# AS226279_ECE319K_Baseline_Schematic.net
KiCad netlist of a schematic drawn in EAGLE
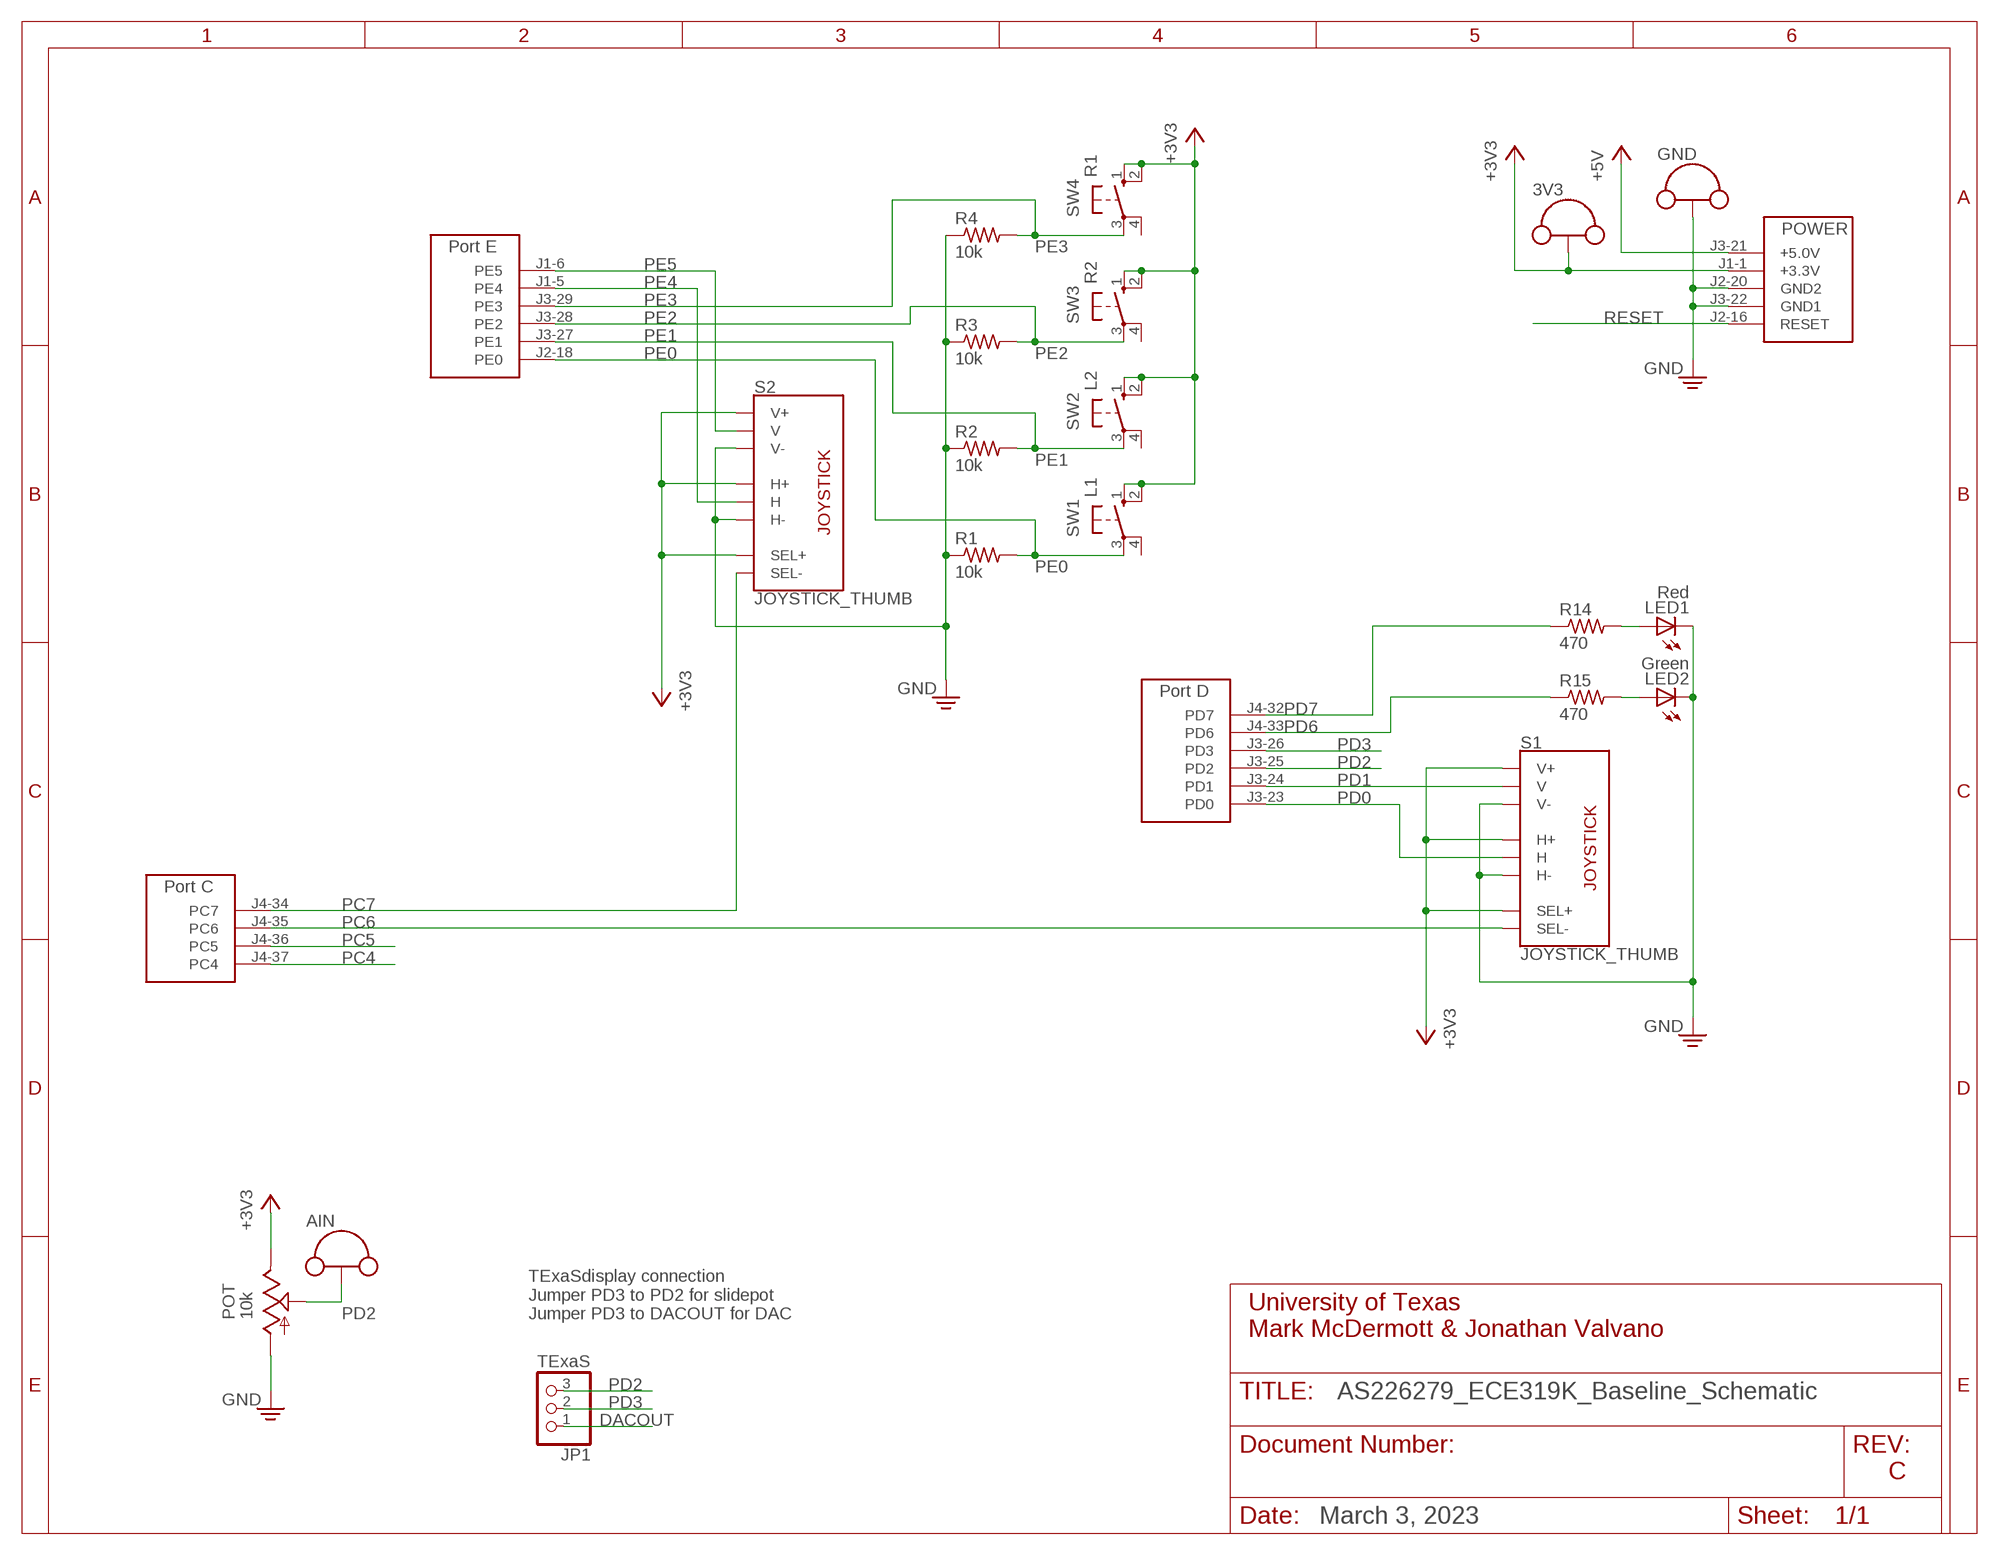
[diagram p0: schematic, sheet 1, part 1 of 2]
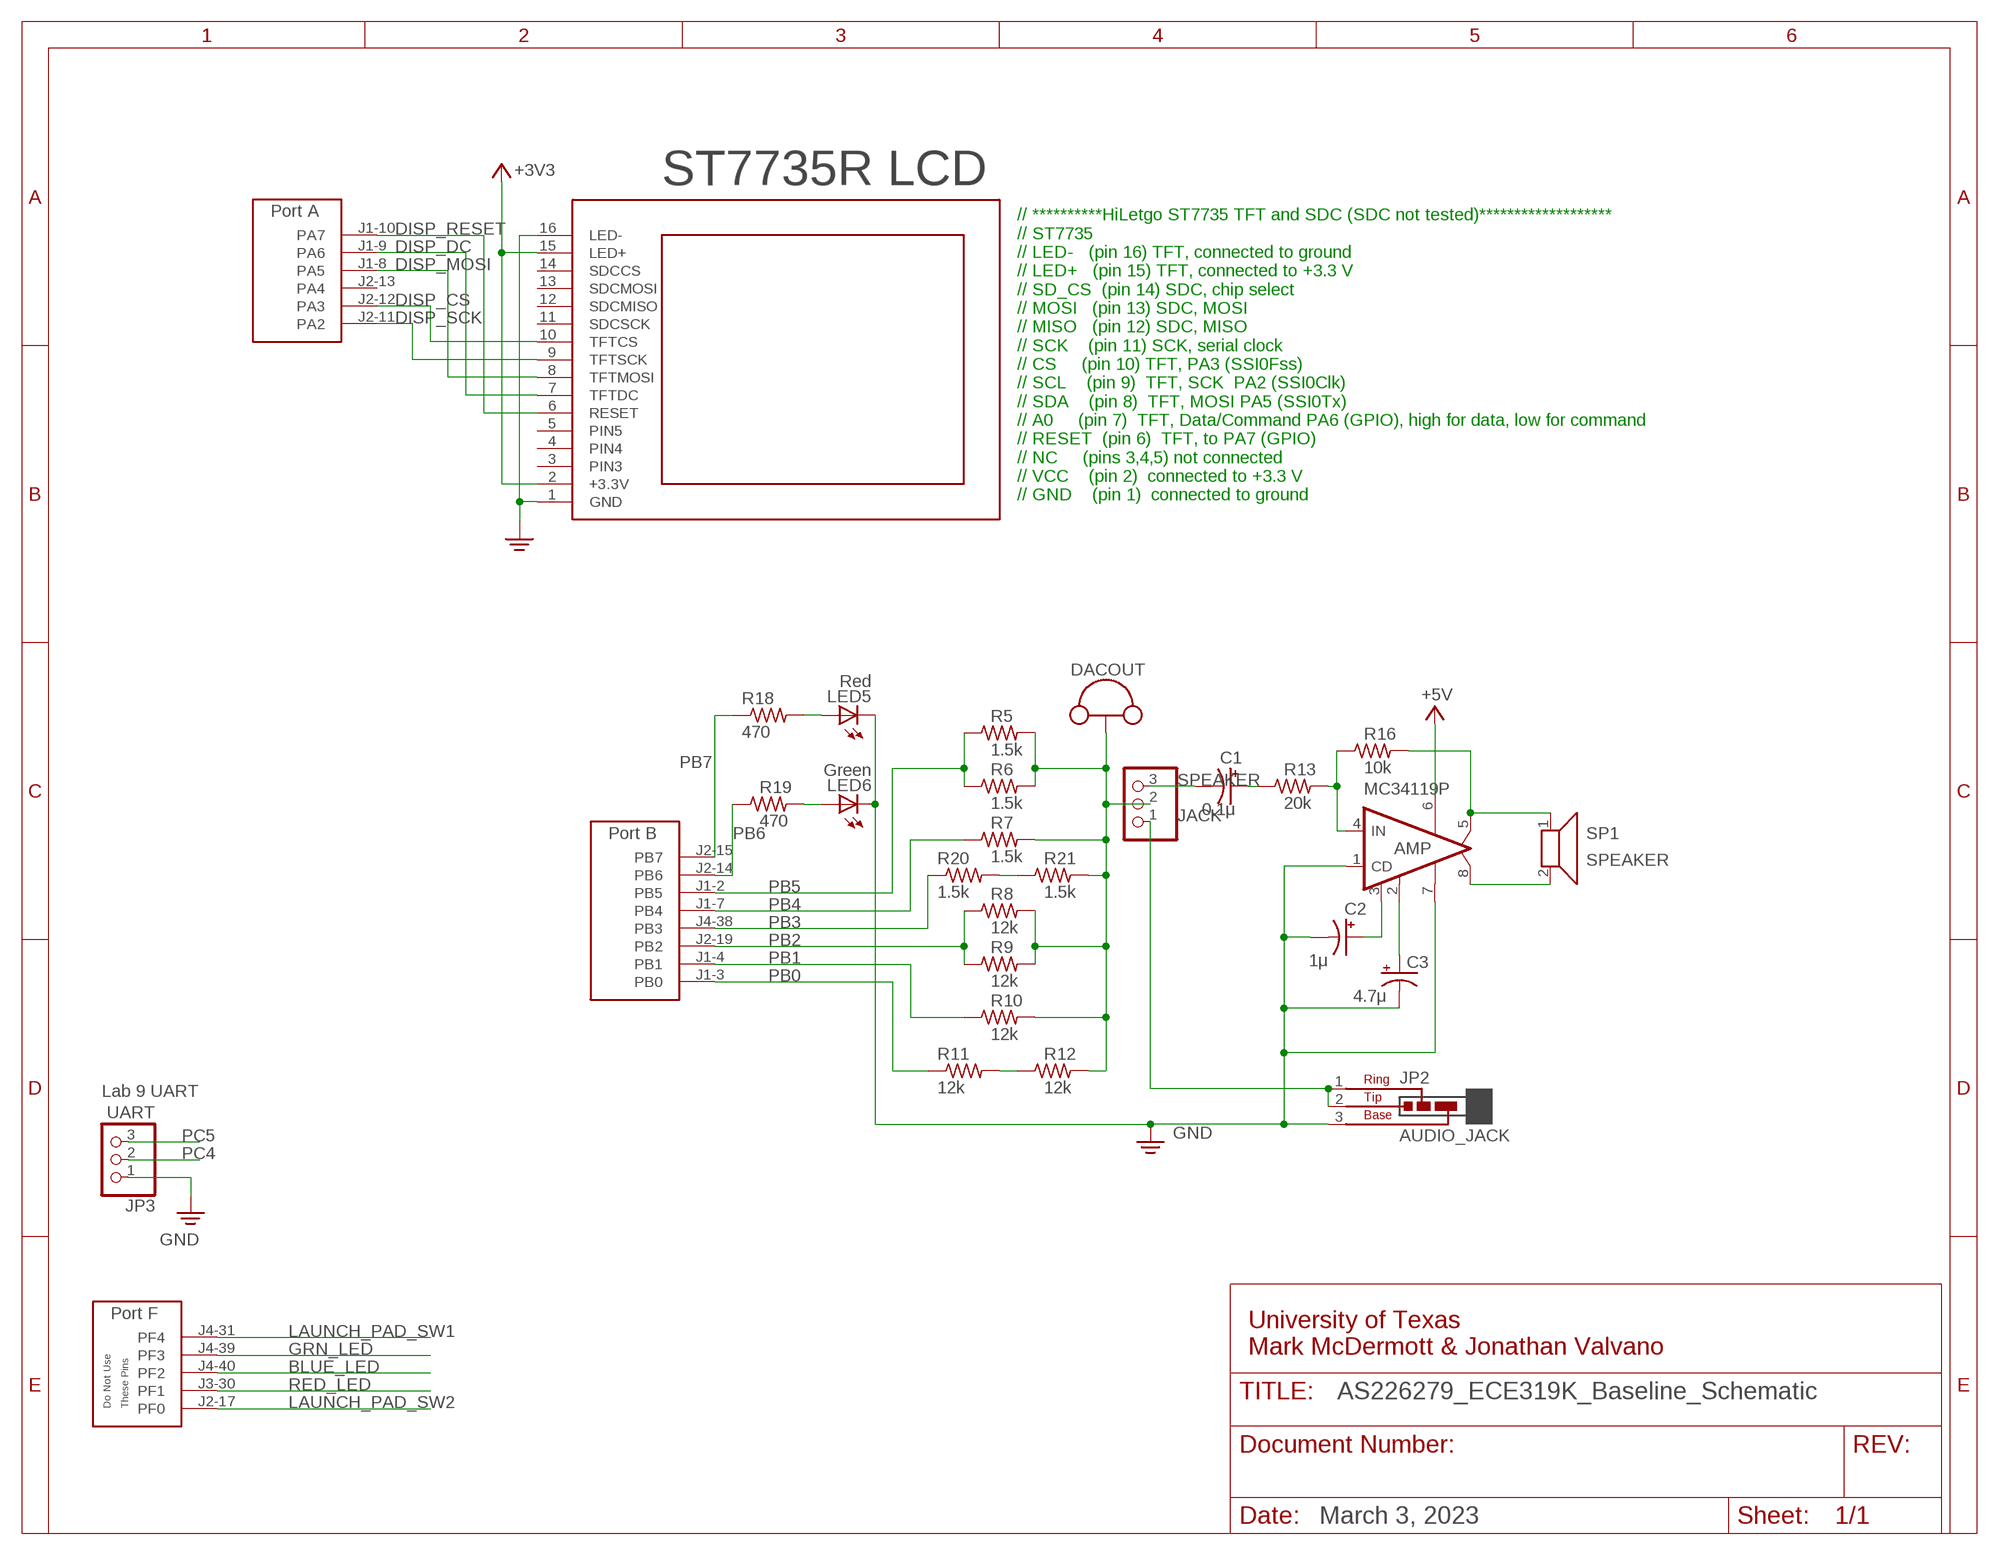
[diagram p1: schematic, sheet 1, part 2 of 2]

(export (version "E")
  (design (tool "Eeschema 10.0.6"))
  (components
    (comp (ref "3V3")
      (value "TP_LOOP")
      (footprint "eagle-import:TP_LOOP")
      (libsource (lib "eagle-import") (part "TP_LOOP"))
    )
    (comp (ref "AIN")
      (value "TP_LOOP")
      (footprint "eagle-import:TP_LOOP")
      (libsource (lib "eagle-import") (part "TP_LOOP"))
    )
    (comp (ref "AMP")
      (value "MC34119P")
      (footprint "eagle-import:DIL08")
      (libsource (lib "eagle-import") (part "MC34119P"))
    )
    (comp (ref "C1")
      (value "0.1μ")
      (footprint "eagle-import:CAP200MILPOLARIZED")
      (libsource (lib "eagle-import") (part "CAPACITOR_POLARIZEDE5-6"))
    )
    (comp (ref "C2")
      (value "1μ")
      (footprint "eagle-import:CAP200MILPOLARIZED")
      (libsource (lib "eagle-import") (part "CAPACITOR_POLARIZEDE5-6"))
    )
    (comp (ref "C3")
      (value "4.7μ")
      (footprint "eagle-import:CAP200MILPOLARIZED")
      (libsource (lib "eagle-import") (part "CAPACITOR_POLARIZEDE5-6"))
    )
    (comp (ref "DACOUT")
      (value "TP_LOOP")
      (footprint "eagle-import:TP_LOOP")
      (libsource (lib "eagle-import") (part "TP_LOOP"))
    )
    (comp (ref "DACOUT_HEADER")
      (value "TExaS")
      (footprint "eagle-import:1X03")
      (libsource (lib "eagle-import") (part "PINHD-1X3"))
    )
    (comp (ref "GND")
      (value "TP_LOOP")
      (footprint "eagle-import:TP_LOOP")
      (libsource (lib "eagle-import") (part "TP_LOOP"))
    )
    (comp (ref "JP1")
      (value "TExaS")
      (footprint "eagle-import:1X03")
      (libsource (lib "eagle-import") (part "PINHD-1X3"))
    )
    (comp (ref "JP2")
      (value "AUDIO_JACK")
      (footprint "eagle-import:JACK")
      (libsource (lib "eagle-import") (part "AUDIO_JACK"))
    )
    (comp (ref "JP3")
      (value "UART")
      (footprint "eagle-import:1X03")
      (libsource (lib "eagle-import") (part "PINHD-1X3"))
    )
    (comp (ref "LED1")
      (value "Red")
      (footprint "eagle-import:LED5MM")
      (libsource (lib "eagle-import") (part "LED5MM"))
    )
    (comp (ref "LED2")
      (value "Green")
      (footprint "eagle-import:LED5MM")
      (libsource (lib "eagle-import") (part "LED5MM"))
    )
    (comp (ref "LED5")
      (value "Red")
      (footprint "eagle-import:LED5MM")
      (libsource (lib "eagle-import") (part "LED5MM"))
    )
    (comp (ref "LED6")
      (value "Green")
      (footprint "eagle-import:LED5MM")
      (libsource (lib "eagle-import") (part "LED5MM"))
    )
    (comp (ref "POT")
      (value "10k")
      (footprint "eagle-import:PTA2043")
      (libsource (lib "eagle-import") (part "POTENTIOMETER_PTA2043B25U"))
    )
    (comp (ref "R1")
      (value "10k")
      (footprint "eagle-import:RES300MIL")
      (libsource (lib "eagle-import") (part "RESISTOR0204/7"))
    )
    (comp (ref "R2")
      (value "10k")
      (footprint "eagle-import:RES300MIL")
      (libsource (lib "eagle-import") (part "RESISTOR0204/7"))
    )
    (comp (ref "R3")
      (value "10k")
      (footprint "eagle-import:RES300MIL")
      (libsource (lib "eagle-import") (part "RESISTOR0204/7"))
    )
    (comp (ref "R4")
      (value "10k")
      (footprint "eagle-import:RES300MIL")
      (libsource (lib "eagle-import") (part "RESISTOR0204/7"))
    )
    (comp (ref "R5")
      (value "1.5k")
      (footprint "eagle-import:RES300MIL")
      (libsource (lib "eagle-import") (part "RESISTOR0204/7"))
    )
    (comp (ref "R6")
      (value "1.5k")
      (footprint "eagle-import:RES300MIL")
      (libsource (lib "eagle-import") (part "RESISTOR0204/7"))
    )
    (comp (ref "R7")
      (value "1.5k")
      (footprint "eagle-import:RES300MIL")
      (libsource (lib "eagle-import") (part "RESISTOR0204/7"))
    )
    (comp (ref "R8")
      (value "12k")
      (footprint "eagle-import:RES300MIL")
      (libsource (lib "eagle-import") (part "RESISTOR0204/7"))
    )
    (comp (ref "R9")
      (value "12k")
      (footprint "eagle-import:RES300MIL")
      (libsource (lib "eagle-import") (part "RESISTOR0204/7"))
    )
    (comp (ref "R10")
      (value "12k")
      (footprint "eagle-import:RES300MIL")
      (libsource (lib "eagle-import") (part "RESISTOR0204/7"))
    )
    (comp (ref "R11")
      (value "12k")
      (footprint "eagle-import:RES300MIL")
      (libsource (lib "eagle-import") (part "RESISTOR0204/7"))
    )
    (comp (ref "R12")
      (value "12k")
      (footprint "eagle-import:RES300MIL")
      (libsource (lib "eagle-import") (part "RESISTOR0204/7"))
    )
    (comp (ref "R13")
      (value "20k")
      (footprint "eagle-import:RES300MIL")
      (libsource (lib "eagle-import") (part "RESISTOR0204/7"))
    )
    (comp (ref "R14")
      (value "470")
      (footprint "eagle-import:RES300MIL")
      (libsource (lib "eagle-import") (part "RESISTOR0204/7"))
    )
    (comp (ref "R15")
      (value "470")
      (footprint "eagle-import:RES300MIL")
      (libsource (lib "eagle-import") (part "RESISTOR0204/7"))
    )
    (comp (ref "R16")
      (value "10k")
      (footprint "eagle-import:RES300MIL")
      (libsource (lib "eagle-import") (part "RESISTOR0204/7"))
    )
    (comp (ref "R18")
      (value "470")
      (footprint "eagle-import:RES300MIL")
      (libsource (lib "eagle-import") (part "RESISTOR0204/7"))
    )
    (comp (ref "R19")
      (value "470")
      (footprint "eagle-import:RES300MIL")
      (libsource (lib "eagle-import") (part "RESISTOR0204/7"))
    )
    (comp (ref "R20")
      (value "1.5k")
      (footprint "eagle-import:RES300MIL")
      (libsource (lib "eagle-import") (part "RESISTOR0204/7"))
    )
    (comp (ref "R21")
      (value "1.5k")
      (footprint "eagle-import:RES300MIL")
      (libsource (lib "eagle-import") (part "RESISTOR0204/7"))
    )
    (comp (ref "S1")
      (value "JOYSTICK_THUMB")
      (footprint "eagle-import:JOYSTICK")
      (libsource (lib "eagle-import") (part "JOYSTICK_THUMB"))
    )
    (comp (ref "S2")
      (value "JOYSTICK_THUMB")
      (footprint "eagle-import:JOYSTICK")
      (libsource (lib "eagle-import") (part "JOYSTICK_THUMB"))
    )
    (comp (ref "SP1")
      (value "SPEAKER")
      (footprint "eagle-import:1X02")
      (libsource (lib "eagle-import") (part "SPEAKER"))
    )
    (comp (ref "SW1")
      (value "L1")
      (footprint "eagle-import:B3F-10XX")
      (fields (field (name "MPN") "B3F-1000"))
      (libsource (lib "eagle-import") (part "B3F-1052"))
    )
    (comp (ref "SW2")
      (value "L2")
      (footprint "eagle-import:B3F-10XX")
      (fields (field (name "MPN") "B3F-1000"))
      (libsource (lib "eagle-import") (part "B3F-1052"))
    )
    (comp (ref "SW3")
      (value "R2")
      (footprint "eagle-import:B3F-10XX")
      (fields (field (name "MPN") "B3F-1000"))
      (libsource (lib "eagle-import") (part "B3F-1052"))
    )
    (comp (ref "SW4")
      (value "R1")
      (footprint "eagle-import:B3F-10XX")
      (fields (field (name "MPN") "B3F-1000"))
      (libsource (lib "eagle-import") (part "B3F-1052"))
    )
    (comp (ref "U$1")
      (value "HILETGO")
      (footprint "eagle-import:HILETGO")
      (libsource (lib "eagle-import") (part "HILETGO"))
    )
    (comp (ref "U$2")
      (value "TM4C_BP")
      (footprint "eagle-import:TM4C_BOOSTER_PACK")
      (libsource (lib "eagle-import") (part "TM4C_BP"))
    )
  )
  (nets
    (net (code "1") (name "+3V3") (class "Default")
      (node (ref "3V3") (pin "P$1") (pinfunction "TP_P$1") (pintype "bidirectional"))
      (node (ref "3V3") (pin "P$2") (pinfunction "TP_P$2") (pintype "bidirectional"))
      (node (ref "POT") (pin "1") (pinfunction "E_1") (pintype "passive"))
      (node (ref "S1") (pin "B1A") (pinfunction "SEL+_B1A") (pintype "bidirectional"))
      (node (ref "S1") (pin "H1") (pinfunction "H+_H1") (pintype "bidirectional"))
      (node (ref "S1") (pin "V1") (pinfunction "V+_V1") (pintype "bidirectional"))
      (node (ref "S2") (pin "B1A") (pinfunction "SEL+_B1A") (pintype "bidirectional"))
      (node (ref "S2") (pin "H1") (pinfunction "H+_H1") (pintype "bidirectional"))
      (node (ref "S2") (pin "V1") (pinfunction "V+_V1") (pintype "bidirectional"))
      (node (ref "SW1") (pin "1") (pinfunction "S_1") (pintype "passive"))
      (node (ref "SW1") (pin "2") (pinfunction "S1_2") (pintype "passive"))
      (node (ref "SW2") (pin "1") (pinfunction "S_1") (pintype "passive"))
      (node (ref "SW2") (pin "2") (pinfunction "S1_2") (pintype "passive"))
      (node (ref "SW3") (pin "1") (pinfunction "S_1") (pintype "passive"))
      (node (ref "SW3") (pin "2") (pinfunction "S1_2") (pintype "passive"))
      (node (ref "SW4") (pin "1") (pinfunction "S_1") (pintype "passive"))
      (node (ref "SW4") (pin "2") (pinfunction "S1_2") (pintype "passive"))
      (node (ref "U$1") (pin "15") (pinfunction "LED+_15") (pintype "bidirectional"))
      (node (ref "U$1") (pin "2") (pinfunction "+3.3V_2") (pintype "bidirectional"))
      (node (ref "U$2") (pin "J1-1") (pinfunction "+3.3V_J1-1") (pintype "bidirectional"))
    )
    (net (code "2") (name "+5V") (class "Default")
      (node (ref "AMP") (pin "6") (pinfunction "VCC_6") (pintype "power_in"))
      (node (ref "U$2") (pin "J3-21") (pinfunction "+5.0V_J3-21") (pintype "bidirectional"))
    )
    (net (code "3") (name "/BLUE_LED") (class "Default")
      (node (ref "U$2") (pin "J4-40") (pinfunction "PF2_J4-40") (pintype "bidirectional"))
    )
    (net (code "4") (name "/DACOUT") (class "Default")
      (node (ref "DACOUT") (pin "P$1") (pinfunction "TP_P$1") (pintype "bidirectional"))
      (node (ref "DACOUT") (pin "P$2") (pinfunction "TP_P$2") (pintype "bidirectional"))
      (node (ref "DACOUT_HEADER") (pin "2") (pinfunction "2_2") (pintype "passive"))
      (node (ref "JP1") (pin "1") (pinfunction "1_1") (pintype "passive"))
      (node (ref "R10") (pin "2") (pinfunction "2_2") (pintype "passive"))
      (node (ref "R12") (pin "2") (pinfunction "2_2") (pintype "passive"))
      (node (ref "R21") (pin "2") (pinfunction "2_2") (pintype "passive"))
      (node (ref "R5") (pin "2") (pinfunction "2_2") (pintype "passive"))
      (node (ref "R6") (pin "2") (pinfunction "2_2") (pintype "passive"))
      (node (ref "R7") (pin "2") (pinfunction "2_2") (pintype "passive"))
      (node (ref "R8") (pin "2") (pinfunction "2_2") (pintype "passive"))
      (node (ref "R9") (pin "2") (pinfunction "2_2") (pintype "passive"))
    )
    (net (code "5") (name "/DISP_CS") (class "Default")
      (node (ref "U$1") (pin "10") (pinfunction "TFTCS_10") (pintype "bidirectional"))
      (node (ref "U$2") (pin "J2-12") (pinfunction "PA3_J2-12") (pintype "bidirectional"))
    )
    (net (code "6") (name "/DISP_DC") (class "Default")
      (node (ref "U$1") (pin "7") (pinfunction "TFTDC_7") (pintype "bidirectional"))
      (node (ref "U$2") (pin "J1-9") (pinfunction "PA6_J1-9") (pintype "bidirectional"))
    )
    (net (code "7") (name "/DISP_MOSI") (class "Default")
      (node (ref "U$1") (pin "8") (pinfunction "TFTMOSI_8") (pintype "bidirectional"))
      (node (ref "U$2") (pin "J1-8") (pinfunction "PA5_J1-8") (pintype "bidirectional"))
    )
    (net (code "8") (name "/DISP_RESET") (class "Default")
      (node (ref "U$1") (pin "6") (pinfunction "RESET_6") (pintype "bidirectional"))
      (node (ref "U$2") (pin "J1-10") (pinfunction "PA7_J1-10") (pintype "bidirectional"))
    )
    (net (code "9") (name "/DISP_SCK") (class "Default")
      (node (ref "U$1") (pin "9") (pinfunction "TFTSCK_9") (pintype "bidirectional"))
      (node (ref "U$2") (pin "J2-11") (pinfunction "PA2_J2-11") (pintype "bidirectional"))
    )
    (net (code "10") (name "/GRN_LED") (class "Default")
      (node (ref "U$2") (pin "J4-39") (pinfunction "PF3_J4-39") (pintype "bidirectional"))
    )
    (net (code "11") (name "/JACK") (class "Default")
      (node (ref "DACOUT_HEADER") (pin "1") (pinfunction "1_1") (pintype "passive"))
      (node (ref "JP2") (pin "1") (pinfunction "RING_1") (pintype "passive"))
      (node (ref "JP2") (pin "2") (pinfunction "TIP_2") (pintype "passive"))
    )
    (net (code "12") (name "/LAUNCH_PAD_SW1") (class "Default")
      (node (ref "U$2") (pin "J4-31") (pinfunction "PF4_J4-31") (pintype "bidirectional"))
    )
    (net (code "13") (name "/LAUNCH_PAD_SW2") (class "Default")
      (node (ref "U$2") (pin "J2-17") (pinfunction "PF0_J2-17") (pintype "bidirectional"))
    )
    (net (code "14") (name "/PB0") (class "Default")
      (node (ref "R11") (pin "1") (pinfunction "1_1") (pintype "passive"))
      (node (ref "U$2") (pin "J1-3") (pinfunction "PB0_J1-3") (pintype "bidirectional"))
    )
    (net (code "15") (name "/PB1") (class "Default")
      (node (ref "R10") (pin "1") (pinfunction "1_1") (pintype "passive"))
      (node (ref "U$2") (pin "J1-4") (pinfunction "PB1_J1-4") (pintype "bidirectional"))
    )
    (net (code "16") (name "/PB2") (class "Default")
      (node (ref "R8") (pin "1") (pinfunction "1_1") (pintype "passive"))
      (node (ref "R9") (pin "1") (pinfunction "1_1") (pintype "passive"))
      (node (ref "U$2") (pin "J2-19") (pinfunction "PB2_J2-19") (pintype "bidirectional"))
    )
    (net (code "17") (name "/PB3") (class "Default")
      (node (ref "R20") (pin "1") (pinfunction "1_1") (pintype "passive"))
      (node (ref "U$2") (pin "J4-38") (pinfunction "PB3_J4-38") (pintype "bidirectional"))
    )
    (net (code "18") (name "/PB4") (class "Default")
      (node (ref "R7") (pin "1") (pinfunction "1_1") (pintype "passive"))
      (node (ref "U$2") (pin "J1-7") (pinfunction "PB4_J1-7") (pintype "bidirectional"))
    )
    (net (code "19") (name "/PB5") (class "Default")
      (node (ref "R5") (pin "1") (pinfunction "1_1") (pintype "passive"))
      (node (ref "R6") (pin "1") (pinfunction "1_1") (pintype "passive"))
      (node (ref "U$2") (pin "J1-2") (pinfunction "PB5_J1-2") (pintype "bidirectional"))
    )
    (net (code "20") (name "/PB6") (class "Default")
      (node (ref "R19") (pin "1") (pinfunction "1_1") (pintype "passive"))
      (node (ref "U$2") (pin "J2-14") (pinfunction "PB6_J2-14") (pintype "bidirectional"))
    )
    (net (code "21") (name "/PB7") (class "Default")
      (node (ref "R18") (pin "1") (pinfunction "1_1") (pintype "passive"))
      (node (ref "U$2") (pin "J2-15") (pinfunction "PB7_J2-15") (pintype "bidirectional"))
    )
    (net (code "22") (name "/PC4") (class "Default")
      (node (ref "JP3") (pin "2") (pinfunction "2_2") (pintype "passive"))
      (node (ref "U$2") (pin "J4-37") (pinfunction "PC4_J4-37") (pintype "bidirectional"))
    )
    (net (code "23") (name "/PC5") (class "Default")
      (node (ref "JP3") (pin "3") (pinfunction "3_3") (pintype "passive"))
      (node (ref "U$2") (pin "J4-36") (pinfunction "PC5_J4-36") (pintype "bidirectional"))
    )
    (net (code "24") (name "/PC6") (class "Default")
      (node (ref "S1") (pin "B2A") (pinfunction "SEL-_B2A") (pintype "bidirectional"))
      (node (ref "U$2") (pin "J4-35") (pinfunction "PC6_J4-35") (pintype "bidirectional"))
    )
    (net (code "25") (name "/PC7") (class "Default")
      (node (ref "S2") (pin "B2A") (pinfunction "SEL-_B2A") (pintype "bidirectional"))
      (node (ref "U$2") (pin "J4-34") (pinfunction "PC7_J4-34") (pintype "bidirectional"))
    )
    (net (code "26") (name "/PD0") (class "Default")
      (node (ref "S1") (pin "H2") (pinfunction "H_H2") (pintype "bidirectional"))
      (node (ref "U$2") (pin "J3-23") (pinfunction "PD0_J3-23") (pintype "bidirectional"))
    )
    (net (code "27") (name "/PD1") (class "Default")
      (node (ref "S1") (pin "V2") (pinfunction "V_V2") (pintype "bidirectional"))
      (node (ref "U$2") (pin "J3-24") (pinfunction "PD1_J3-24") (pintype "bidirectional"))
    )
    (net (code "28") (name "/PD2") (class "Default")
      (node (ref "AIN") (pin "P$1") (pinfunction "TP_P$1") (pintype "bidirectional"))
      (node (ref "AIN") (pin "P$2") (pinfunction "TP_P$2") (pintype "bidirectional"))
      (node (ref "JP1") (pin "3") (pinfunction "3_3") (pintype "passive"))
      (node (ref "POT") (pin "2") (pinfunction "S_2") (pintype "passive"))
      (node (ref "U$2") (pin "J3-25") (pinfunction "PD2_J3-25") (pintype "bidirectional"))
    )
    (net (code "29") (name "/PD3") (class "Default")
      (node (ref "JP1") (pin "2") (pinfunction "2_2") (pintype "passive"))
      (node (ref "U$2") (pin "J3-26") (pinfunction "PD3_J3-26") (pintype "bidirectional"))
    )
    (net (code "30") (name "/PD6") (class "Default")
      (node (ref "R15") (pin "1") (pinfunction "1_1") (pintype "passive"))
      (node (ref "U$2") (pin "J4-33") (pinfunction "PD6_J4-33") (pintype "bidirectional"))
    )
    (net (code "31") (name "/PD7") (class "Default")
      (node (ref "R14") (pin "1") (pinfunction "1_1") (pintype "passive"))
      (node (ref "U$2") (pin "J4-32") (pinfunction "PD7_J4-32") (pintype "bidirectional"))
    )
    (net (code "32") (name "/PE0") (class "Default")
      (node (ref "R1") (pin "2") (pinfunction "2_2") (pintype "passive"))
      (node (ref "SW1") (pin "3") (pinfunction "P_3") (pintype "passive"))
      (node (ref "U$2") (pin "J2-18") (pinfunction "PE0_J2-18") (pintype "bidirectional"))
    )
    (net (code "33") (name "/PE1") (class "Default")
      (node (ref "R2") (pin "2") (pinfunction "2_2") (pintype "passive"))
      (node (ref "SW2") (pin "3") (pinfunction "P_3") (pintype "passive"))
      (node (ref "U$2") (pin "J3-27") (pinfunction "PE1_J3-27") (pintype "bidirectional"))
    )
    (net (code "34") (name "/PE2") (class "Default")
      (node (ref "R3") (pin "2") (pinfunction "2_2") (pintype "passive"))
      (node (ref "SW3") (pin "3") (pinfunction "P_3") (pintype "passive"))
      (node (ref "U$2") (pin "J3-28") (pinfunction "PE2_J3-28") (pintype "bidirectional"))
    )
    (net (code "35") (name "/PE3") (class "Default")
      (node (ref "R4") (pin "2") (pinfunction "2_2") (pintype "passive"))
      (node (ref "SW4") (pin "3") (pinfunction "P_3") (pintype "passive"))
      (node (ref "U$2") (pin "J3-29") (pinfunction "PE3_J3-29") (pintype "bidirectional"))
    )
    (net (code "36") (name "/PE4") (class "Default")
      (node (ref "S2") (pin "H2") (pinfunction "H_H2") (pintype "bidirectional"))
      (node (ref "U$2") (pin "J1-5") (pinfunction "PE4_J1-5") (pintype "bidirectional"))
    )
    (net (code "37") (name "/PE5") (class "Default")
      (node (ref "S2") (pin "V2") (pinfunction "V_V2") (pintype "bidirectional"))
      (node (ref "U$2") (pin "J1-6") (pinfunction "PE5_J1-6") (pintype "bidirectional"))
    )
    (net (code "38") (name "/RED_LED") (class "Default")
      (node (ref "U$2") (pin "J3-30") (pinfunction "PF1_J3-30") (pintype "bidirectional"))
    )
    (net (code "39") (name "/RESET") (class "Default")
      (node (ref "U$2") (pin "J2-16") (pinfunction "RESET_J2-16") (pintype "bidirectional"))
    )
    (net (code "40") (name "/SPEAKER") (class "Default")
      (node (ref "C1") (pin "-") (pinfunction "-_-") (pintype "passive"))
      (node (ref "DACOUT_HEADER") (pin "3") (pinfunction "3_3") (pintype "passive"))
    )
    (net (code "41") (name "GND") (class "Default")
      (node (ref "AMP") (pin "1") (pinfunction "CD_1") (pintype "passive"))
      (node (ref "AMP") (pin "7") (pinfunction "GND_7") (pintype "power_in"))
      (node (ref "C2") (pin "-") (pinfunction "-_-") (pintype "passive"))
      (node (ref "C3") (pin "-") (pinfunction "-_-") (pintype "passive"))
      (node (ref "GND") (pin "P$1") (pinfunction "TP_P$1") (pintype "bidirectional"))
      (node (ref "GND") (pin "P$2") (pinfunction "TP_P$2") (pintype "bidirectional"))
      (node (ref "JP2") (pin "3") (pinfunction "BASE_3") (pintype "passive"))
      (node (ref "JP3") (pin "1") (pinfunction "1_1") (pintype "passive"))
      (node (ref "LED1") (pin "K") (pinfunction "C_K") (pintype "passive"))
      (node (ref "LED2") (pin "K") (pinfunction "C_K") (pintype "passive"))
      (node (ref "LED5") (pin "K") (pinfunction "C_K") (pintype "passive"))
      (node (ref "LED6") (pin "K") (pinfunction "C_K") (pintype "passive"))
      (node (ref "POT") (pin "3") (pinfunction "A_3") (pintype "passive"))
      (node (ref "R1") (pin "1") (pinfunction "1_1") (pintype "passive"))
      (node (ref "R2") (pin "1") (pinfunction "1_1") (pintype "passive"))
      (node (ref "R3") (pin "1") (pinfunction "1_1") (pintype "passive"))
      (node (ref "R4") (pin "1") (pinfunction "1_1") (pintype "passive"))
      (node (ref "S1") (pin "H3") (pinfunction "H-_H3") (pintype "bidirectional"))
      (node (ref "S1") (pin "V3") (pinfunction "V-_V3") (pintype "bidirectional"))
      (node (ref "S2") (pin "H3") (pinfunction "H-_H3") (pintype "bidirectional"))
      (node (ref "S2") (pin "V3") (pinfunction "V-_V3") (pintype "bidirectional"))
      (node (ref "U$1") (pin "1") (pinfunction "GND_1") (pintype "bidirectional"))
      (node (ref "U$1") (pin "16") (pinfunction "LED-_16") (pintype "bidirectional"))
      (node (ref "U$2") (pin "J2-20") (pinfunction "GND2_J2-20") (pintype "bidirectional"))
      (node (ref "U$2") (pin "J3-22") (pinfunction "GND1_J3-22") (pintype "bidirectional"))
    )
    (net (code "42") (name "Net-(AMP-FC1)") (class "Default")
      (node (ref "AMP") (pin "3") (pinfunction "FC1_3") (pintype "passive"))
      (node (ref "C2") (pin "+") (pinfunction "+_+") (pintype "passive"))
    )
    (net (code "43") (name "Net-(AMP-FC2)") (class "Default")
      (node (ref "AMP") (pin "2") (pinfunction "FC2_2") (pintype "passive"))
      (node (ref "C3") (pin "+") (pinfunction "+_+") (pintype "passive"))
    )
    (net (code "44") (name "Net-(AMP-IN)") (class "Default")
      (node (ref "AMP") (pin "4") (pinfunction "IN_4") (pintype "input"))
      (node (ref "R13") (pin "2") (pinfunction "2_2") (pintype "passive"))
      (node (ref "R16") (pin "1") (pinfunction "1_1") (pintype "passive"))
    )
    (net (code "45") (name "Net-(AMP-VO1)") (class "Default")
      (node (ref "AMP") (pin "5") (pinfunction "VO1_5") (pintype "output"))
      (node (ref "R16") (pin "2") (pinfunction "2_2") (pintype "passive"))
      (node (ref "SP1") (pin "1") (pinfunction "1_1") (pintype "passive"))
    )
    (net (code "46") (name "Net-(AMP-VO2)") (class "Default")
      (node (ref "AMP") (pin "8") (pinfunction "VO2_8") (pintype "output"))
      (node (ref "SP1") (pin "2") (pinfunction "2_2") (pintype "passive"))
    )
    (net (code "47") (name "Net-(C1-Pad+)") (class "Default")
      (node (ref "C1") (pin "+") (pinfunction "+_+") (pintype "passive"))
      (node (ref "R13") (pin "1") (pinfunction "1_1") (pintype "passive"))
    )
    (net (code "48") (name "Net-(LED1-PadA)") (class "Default")
      (node (ref "LED1") (pin "A") (pinfunction "A_A") (pintype "passive"))
      (node (ref "R14") (pin "2") (pinfunction "2_2") (pintype "passive"))
    )
    (net (code "49") (name "Net-(LED2-PadA)") (class "Default")
      (node (ref "LED2") (pin "A") (pinfunction "A_A") (pintype "passive"))
      (node (ref "R15") (pin "2") (pinfunction "2_2") (pintype "passive"))
    )
    (net (code "50") (name "Net-(LED5-PadA)") (class "Default")
      (node (ref "LED5") (pin "A") (pinfunction "A_A") (pintype "passive"))
      (node (ref "R18") (pin "2") (pinfunction "2_2") (pintype "passive"))
    )
    (net (code "51") (name "Net-(LED6-PadA)") (class "Default")
      (node (ref "LED6") (pin "A") (pinfunction "A_A") (pintype "passive"))
      (node (ref "R19") (pin "2") (pinfunction "2_2") (pintype "passive"))
    )
    (net (code "52") (name "Net-(R11-Pad2)") (class "Default")
      (node (ref "R11") (pin "2") (pinfunction "2_2") (pintype "passive"))
      (node (ref "R12") (pin "1") (pinfunction "1_1") (pintype "passive"))
    )
    (net (code "53") (name "Net-(R20-Pad2)") (class "Default")
      (node (ref "R20") (pin "2") (pinfunction "2_2") (pintype "passive"))
      (node (ref "R21") (pin "1") (pinfunction "1_1") (pintype "passive"))
    )
    (net (code "54") (name "unconnected-(SW1-P1-Pad4)") (class "Default")
      (node (ref "SW1") (pin "4") (pinfunction "P1_4") (pintype "passive"))
    )
    (net (code "55") (name "unconnected-(SW2-P1-Pad4)") (class "Default")
      (node (ref "SW2") (pin "4") (pinfunction "P1_4") (pintype "passive"))
    )
    (net (code "56") (name "unconnected-(SW3-P1-Pad4)") (class "Default")
      (node (ref "SW3") (pin "4") (pinfunction "P1_4") (pintype "passive"))
    )
    (net (code "57") (name "unconnected-(SW4-P1-Pad4)") (class "Default")
      (node (ref "SW4") (pin "4") (pinfunction "P1_4") (pintype "passive"))
    )
    (net (code "58") (name "unconnected-(U$1-PIN3-Pad3)") (class "Default")
      (node (ref "U$1") (pin "3") (pinfunction "PIN3_3") (pintype "bidirectional"))
    )
    (net (code "59") (name "unconnected-(U$1-PIN4-Pad4)") (class "Default")
      (node (ref "U$1") (pin "4") (pinfunction "PIN4_4") (pintype "bidirectional"))
    )
    (net (code "60") (name "unconnected-(U$1-PIN5-Pad5)") (class "Default")
      (node (ref "U$1") (pin "5") (pinfunction "PIN5_5") (pintype "bidirectional"))
    )
    (net (code "61") (name "unconnected-(U$1-SDCCS-Pad14)") (class "Default")
      (node (ref "U$1") (pin "14") (pinfunction "SDCCS_14") (pintype "bidirectional"))
    )
    (net (code "62") (name "unconnected-(U$1-SDCMISO-Pad12)") (class "Default")
      (node (ref "U$1") (pin "12") (pinfunction "SDCMISO_12") (pintype "bidirectional"))
    )
    (net (code "63") (name "unconnected-(U$1-SDCMOSI-Pad13)") (class "Default")
      (node (ref "U$1") (pin "13") (pinfunction "SDCMOSI_13") (pintype "bidirectional"))
    )
    (net (code "64") (name "unconnected-(U$1-SDCSCK-Pad11)") (class "Default")
      (node (ref "U$1") (pin "11") (pinfunction "SDCSCK_11") (pintype "bidirectional"))
    )
    (net (code "65") (name "unconnected-(U$2A-PA4-PadJ2-13)") (class "Default")
      (node (ref "U$2") (pin "J2-13") (pinfunction "PA4_J2-13") (pintype "bidirectional"))
    )
  )
)
